# 3V3_Low_Dropout__Regulator.net
KiCad netlist of a schematic drawn in Altium Designer
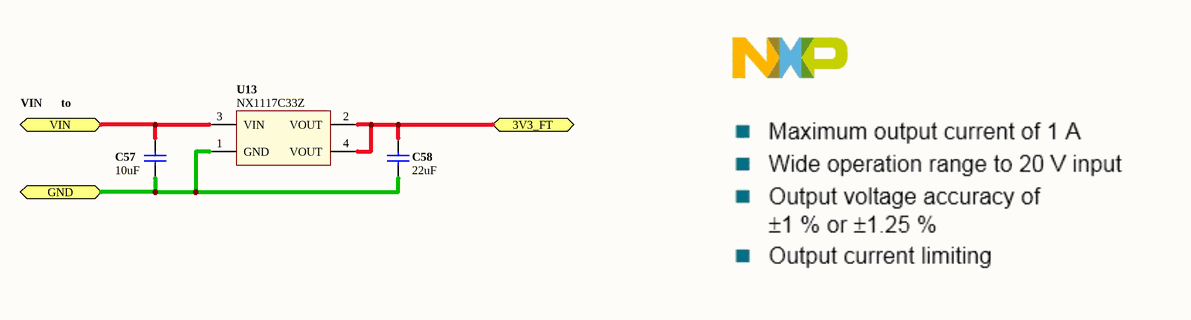
[diagram p0: 3V3_Low_Dropout_ Regulator.SchDoc]

(export (version "E")
  (design (tool "Eeschema 10.0.6"))
  (components
    (comp (ref "C57")
      (value "10uF")
      (footprint "CAPC0805(2012)100_N")
      (description "CAP 10uF 10V ?0% 0805 (2012 Metric) Thickness 1mm SMD")
      (fields (field (name "TOLERANCE") "?0%") (field (name "Comment") "CAP 10uF 10V 0805(2012)"))
      (libsource (lib "Altium Content Vault") (part "CMP-1036-04925-1"))
    )
    (comp (ref "C58")
      (value "22uF")
      (footprint "CAPC1206(3216)100_L")
      (description "CAP 22uF 6.3V ?0% 1206 (3216 Metric) Thickness 1mm SMD")
      (fields (field (name "TOLERANCE") "?0%") (field (name "Comment") "CAP 22uF 6.3V 1206(3216)"))
      (libsource (lib "Altium Content Vault") (part "CMP-1037-04987-1"))
    )
    (comp (ref "U13")
      (value "NX1117C33Z")
      (footprint "NXP-SOT223")
      (description "Low-dropout linear regulator, 3.3V Output, SOT223")
      (libsource (lib "Altium Content Vault") (part "CMP-5296-00001-1"))
    )
  )
  (nets
    (net (code "1") (name "/3V3_FT") (class "Default")
      (node (ref "C58") (pin "2") (pinfunction "2_2") (pintype "passive"))
      (node (ref "U13") (pin "2") (pinfunction "VOUT_2") (pintype "power_in"))
      (node (ref "U13") (pin "4") (pinfunction "VOUT_4") (pintype "power_in"))
    )
    (net (code "2") (name "/GND") (class "Default")
      (node (ref "C57") (pin "1") (pinfunction "1_1") (pintype "passive"))
      (node (ref "C58") (pin "1") (pinfunction "1_1") (pintype "passive"))
      (node (ref "U13") (pin "1") (pinfunction "GND_1") (pintype "power_in"))
    )
    (net (code "3") (name "/VIN") (class "Default")
      (node (ref "C57") (pin "2") (pinfunction "2_2") (pintype "passive"))
      (node (ref "U13") (pin "3") (pinfunction "VIN_3") (pintype "power_in"))
    )
  )
)
